# I2C_Ext.net
KiCad netlist of a schematic drawn in EAGLE
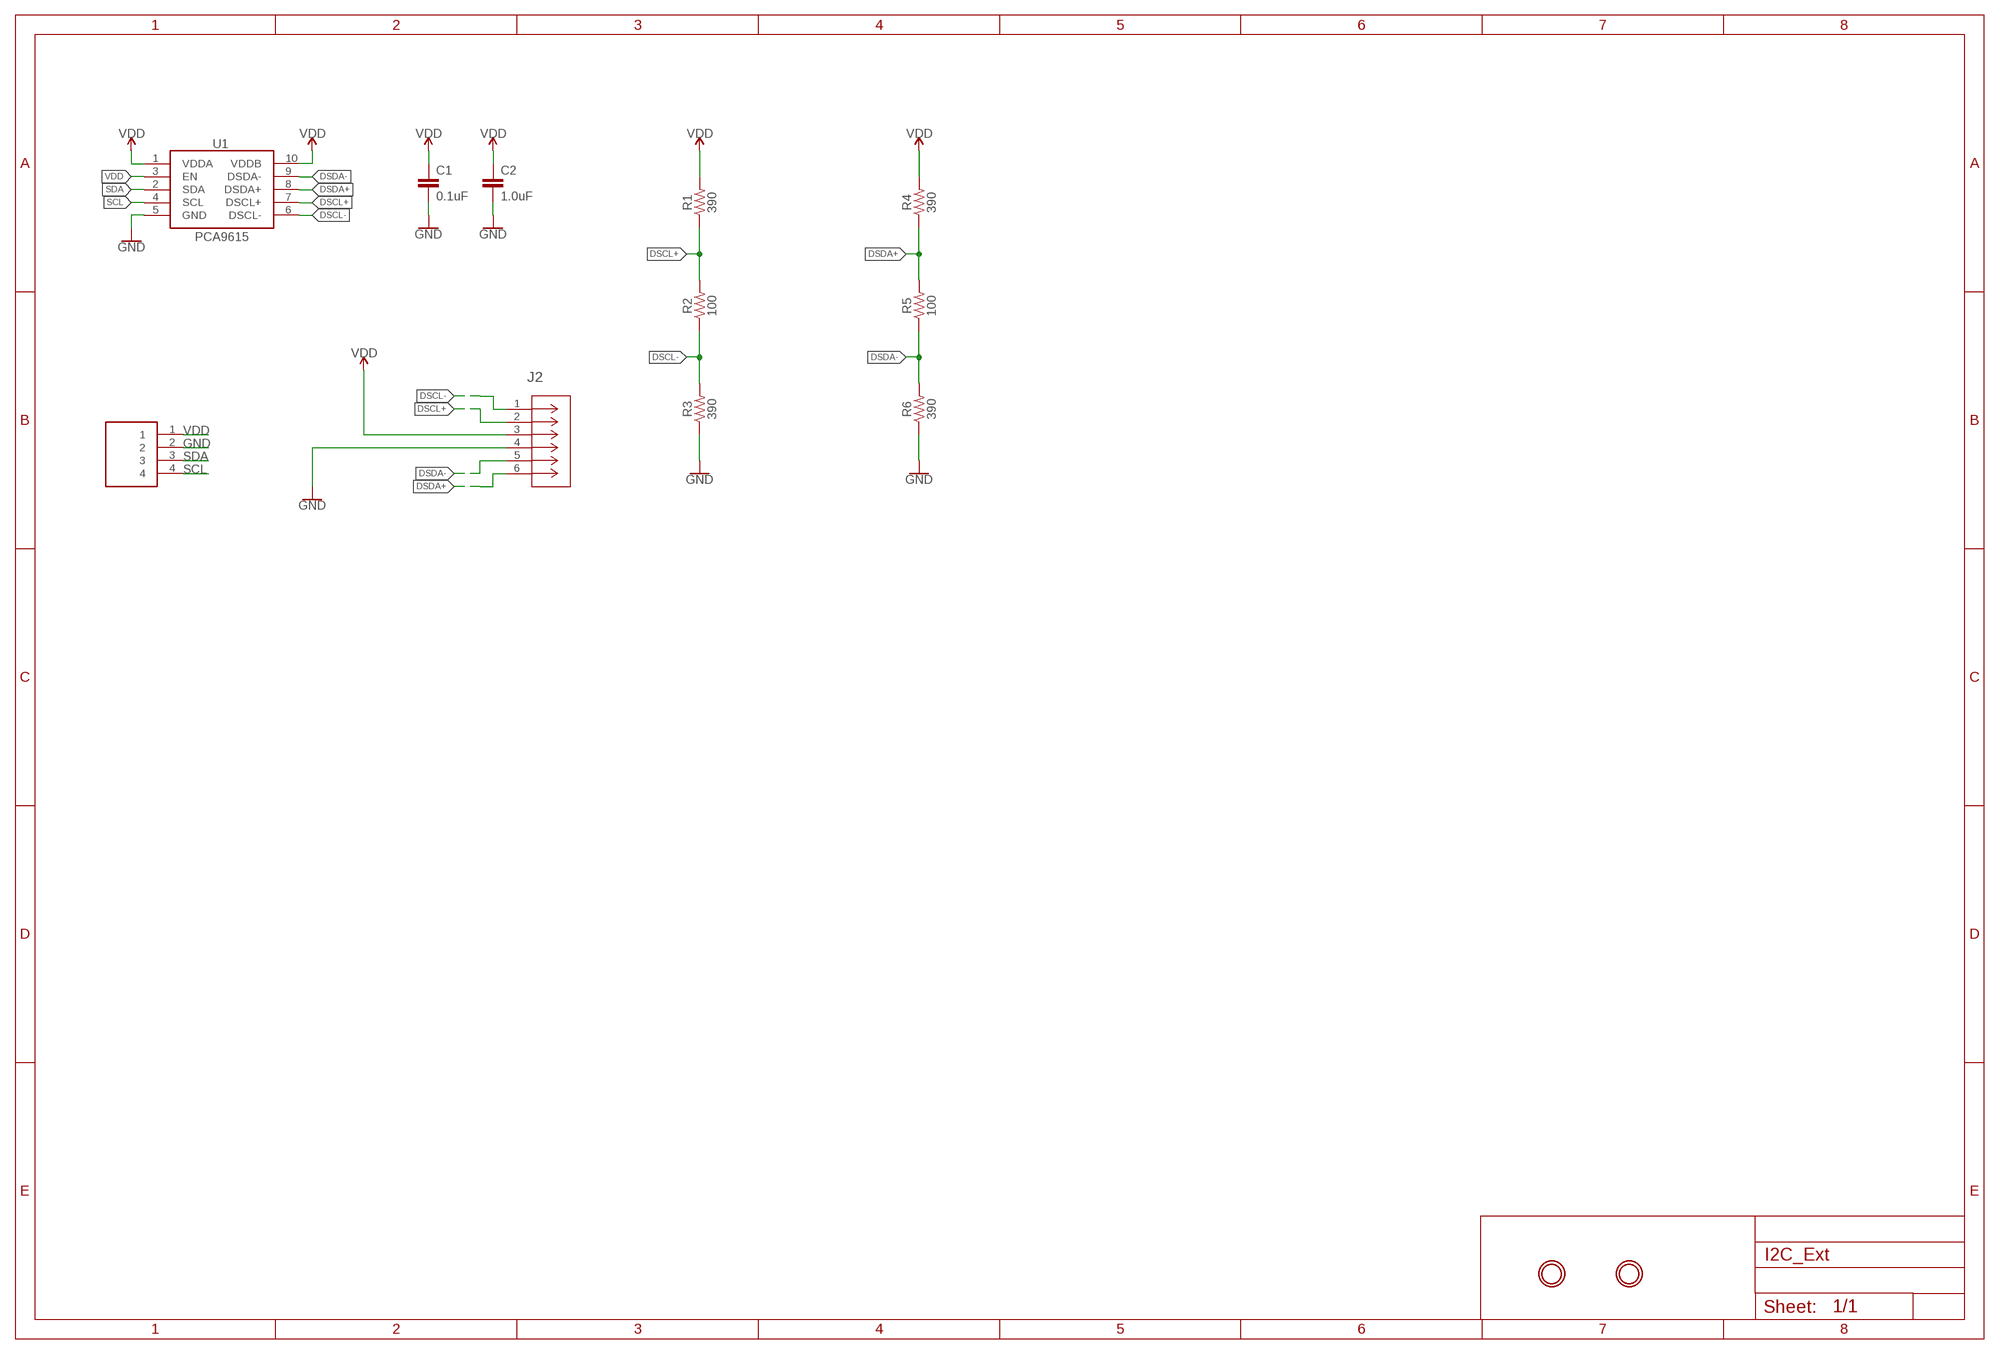
[diagram p0: schematic, sheet 1]

(export (version "E")
  (design (tool "Eeschema 10.0.6"))
  (components
    (comp (ref "C1")
      (value "0.1uF")
      (footprint "eagle-import:0603")
      (libsource (lib "eagle-import") (part "0.1UF-0603-25V-(+80/-20%)"))
    )
    (comp (ref "C2")
      (value "1.0uF")
      (footprint "eagle-import:0603")
      (libsource (lib "eagle-import") (part "0.1UF-0603-25V-(+80/-20%)"))
    )
    (comp (ref "J1")
      (value "1725672")
      (footprint "eagle-import:1725672")
      (fields (field (name "MOUSER_PART_NUMBER") "651-1725672"))
      (libsource (lib "eagle-import") (part "1725672"))
    )
    (comp (ref "J2")
      (value "1725698")
      (footprint "eagle-import:CONN_1725698_PXC")
      (fields (field (name "COPYRIGHT") "Copyright (C) 2023 Ultra Librarian. All rights reserved."))
      (libsource (lib "eagle-import") (part "1725698"))
    )
    (comp (ref "R1")
      (value "390")
      (footprint "eagle-import:0603")
      (libsource (lib "eagle-import") (part "390OHM-0603-1/10W-1%"))
    )
    (comp (ref "R2")
      (value "100")
      (footprint "eagle-import:0603")
      (libsource (lib "eagle-import") (part "100OHM-0603-1/10W-1%"))
    )
    (comp (ref "R3")
      (value "390")
      (footprint "eagle-import:0603")
      (libsource (lib "eagle-import") (part "390OHM-0603-1/10W-1%"))
    )
    (comp (ref "R4")
      (value "390")
      (footprint "eagle-import:0603")
      (libsource (lib "eagle-import") (part "390OHM-0603-1/10W-1%"))
    )
    (comp (ref "R5")
      (value "100")
      (footprint "eagle-import:0603")
      (libsource (lib "eagle-import") (part "100OHM-0603-1/10W-1%"))
    )
    (comp (ref "R6")
      (value "390")
      (footprint "eagle-import:0603")
      (libsource (lib "eagle-import") (part "390OHM-0603-1/10W-1%"))
    )
    (comp (ref "U$1")
      (value "MOUNTINGHOLE2.5")
      (footprint "eagle-import:MOUNTINGHOLE_2.5_PLATED")
      (libsource (lib "eagle-import") (part "MOUNTINGHOLE2.5"))
    )
    (comp (ref "U$3")
      (value "MOUNTINGHOLE2.5")
      (footprint "eagle-import:MOUNTINGHOLE_2.5_PLATED")
      (libsource (lib "eagle-import") (part "MOUNTINGHOLE2.5"))
    )
    (comp (ref "U1")
      (value "PCA9615")
      (footprint "eagle-import:TSSOP10")
      (libsource (lib "eagle-import") (part "PCA9615"))
    )
  )
  (nets
    (net (code "1") (name "DSCL+") (class "Default")
      (node (ref "J2") (pin "2") (pinfunction "2_2") (pintype "passive"))
      (node (ref "R1") (pin "1") (pinfunction "1_1") (pintype "passive"))
      (node (ref "R2") (pin "2") (pinfunction "2_2") (pintype "passive"))
      (node (ref "U1") (pin "7") (pinfunction "DSCL+_7") (pintype "bidirectional"))
    )
    (net (code "2") (name "DSCL-") (class "Default")
      (node (ref "J2") (pin "1") (pinfunction "1_1") (pintype "passive"))
      (node (ref "R2") (pin "1") (pinfunction "1_1") (pintype "passive"))
      (node (ref "R3") (pin "2") (pinfunction "2_2") (pintype "passive"))
      (node (ref "U1") (pin "6") (pinfunction "DSCL-_6") (pintype "bidirectional"))
    )
    (net (code "3") (name "DSDA+") (class "Default")
      (node (ref "J2") (pin "6") (pinfunction "6_6") (pintype "passive"))
      (node (ref "R4") (pin "1") (pinfunction "1_1") (pintype "passive"))
      (node (ref "R5") (pin "2") (pinfunction "2_2") (pintype "passive"))
      (node (ref "U1") (pin "8") (pinfunction "DSDA+_8") (pintype "bidirectional"))
    )
    (net (code "4") (name "DSDA-") (class "Default")
      (node (ref "J2") (pin "5") (pinfunction "5_5") (pintype "passive"))
      (node (ref "R5") (pin "1") (pinfunction "1_1") (pintype "passive"))
      (node (ref "R6") (pin "2") (pinfunction "2_2") (pintype "passive"))
      (node (ref "U1") (pin "9") (pinfunction "DSDA-_9") (pintype "bidirectional"))
    )
    (net (code "5") (name "GND") (class "Default")
      (node (ref "C1") (pin "2") (pinfunction "2_2") (pintype "passive"))
      (node (ref "C2") (pin "2") (pinfunction "2_2") (pintype "passive"))
      (node (ref "J1") (pin "2") (pinfunction "2_2") (pintype "bidirectional"))
      (node (ref "J2") (pin "4") (pinfunction "4_4") (pintype "passive"))
      (node (ref "R3") (pin "1") (pinfunction "1_1") (pintype "passive"))
      (node (ref "R6") (pin "1") (pinfunction "1_1") (pintype "passive"))
      (node (ref "U1") (pin "5") (pinfunction "GND_5") (pintype "bidirectional"))
    )
    (net (code "6") (name "SCL") (class "Default")
      (node (ref "J1") (pin "4") (pinfunction "4_4") (pintype "bidirectional"))
      (node (ref "U1") (pin "4") (pinfunction "SCL_4") (pintype "bidirectional"))
    )
    (net (code "7") (name "SDA") (class "Default")
      (node (ref "J1") (pin "3") (pinfunction "3_3") (pintype "bidirectional"))
      (node (ref "U1") (pin "2") (pinfunction "SDA_2") (pintype "bidirectional"))
    )
    (net (code "8") (name "VDD") (class "Default")
      (node (ref "C1") (pin "1") (pinfunction "1_1") (pintype "passive"))
      (node (ref "C2") (pin "1") (pinfunction "1_1") (pintype "passive"))
      (node (ref "J1") (pin "1") (pinfunction "1_1") (pintype "bidirectional"))
      (node (ref "J2") (pin "3") (pinfunction "3_3") (pintype "passive"))
      (node (ref "R1") (pin "2") (pinfunction "2_2") (pintype "passive"))
      (node (ref "R4") (pin "2") (pinfunction "2_2") (pintype "passive"))
      (node (ref "U1") (pin "1") (pinfunction "VDDA_1") (pintype "bidirectional"))
      (node (ref "U1") (pin "10") (pinfunction "VDDB_10") (pintype "bidirectional"))
      (node (ref "U1") (pin "3") (pinfunction "EN_3") (pintype "bidirectional"))
    )
  )
)
